# EPF-100_MP3.net
KiCad netlist of a schematic drawn in Altium Designer
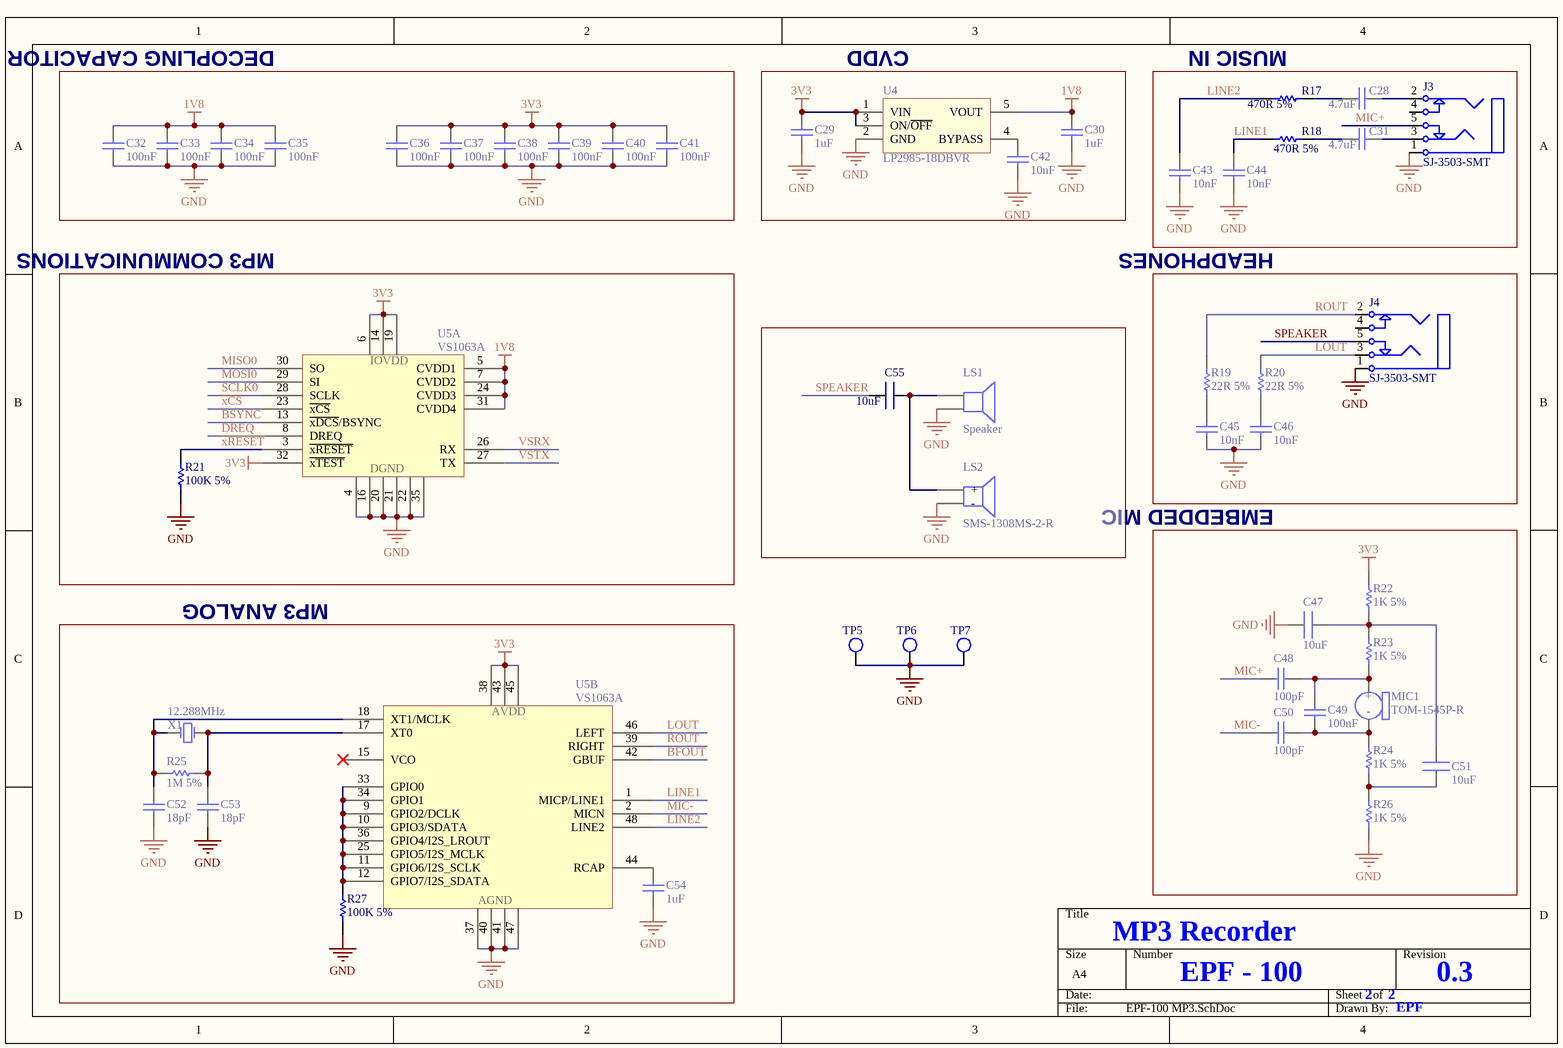
[diagram p0: EPF-100 MP3.SchDoc]

(export (version "E")
  (design (tool "Eeschema 10.0.6"))
  (components
    (comp (ref "C28")
      (value "4.7uF")
      (footprint "CAP0603")
      (description "X7R Ceramic Capacitors - SMD 0603")
      (fields (field (name "TOLERANCE") "X7R") (field (name "MANUFACTURER") "Murata Electronics"))
      (libsource (lib "Glober_Library") (part "CAP 4.7uF"))
    )
    (comp (ref "C29")
      (value "1uF")
      (footprint "CAP0603")
      (description "X7R Ceramic Capacitors - SMD 0603")
      (fields (field (name "TOLERANCE") "X7R") (field (name "MANUFACTURER") "TDK"))
      (libsource (lib "Glober_Library") (part "CAP 1uF"))
    )
    (comp (ref "C30")
      (value "1uF")
      (footprint "CAP0603")
      (description "X7R Ceramic Capacitors - SMD 0603")
      (fields (field (name "TOLERANCE") "X7R") (field (name "MANUFACTURER") "TDK"))
      (libsource (lib "Glober_Library") (part "CAP 1uF"))
    )
    (comp (ref "C31")
      (value "4.7uF")
      (footprint "CAP0603")
      (description "X7R Ceramic Capacitors - SMD 0603")
      (fields (field (name "TOLERANCE") "X7R") (field (name "MANUFACTURER") "Murata Electronics"))
      (libsource (lib "Glober_Library") (part "CAP 4.7uF"))
    )
    (comp (ref "C32")
      (value "100nF")
      (footprint "CAP0603")
      (description "X7R Ceramic Capacitors - SMD 0603")
      (fields (field (name "TOLERANCE") "X7R") (field (name "MANUFACTURER") "TDK"))
      (libsource (lib "Glober_Library") (part "CAP 100nF"))
    )
    (comp (ref "C33")
      (value "100nF")
      (footprint "CAP0603")
      (description "X7R Ceramic Capacitors - SMD 0603")
      (fields (field (name "TOLERANCE") "X7R") (field (name "MANUFACTURER") "TDK"))
      (libsource (lib "Glober_Library") (part "CAP 100nF"))
    )
    (comp (ref "C34")
      (value "100nF")
      (footprint "CAP0603")
      (description "X7R Ceramic Capacitors - SMD 0603")
      (fields (field (name "TOLERANCE") "X7R") (field (name "MANUFACTURER") "TDK"))
      (libsource (lib "Glober_Library") (part "CAP 100nF"))
    )
    (comp (ref "C35")
      (value "100nF")
      (footprint "CAP0603")
      (description "X7R Ceramic Capacitors - SMD 0603")
      (fields (field (name "TOLERANCE") "X7R") (field (name "MANUFACTURER") "TDK"))
      (libsource (lib "Glober_Library") (part "CAP 100nF"))
    )
    (comp (ref "C36")
      (value "100nF")
      (footprint "CAP0603")
      (description "X7R Ceramic Capacitors - SMD 0603")
      (fields (field (name "TOLERANCE") "X7R") (field (name "MANUFACTURER") "TDK"))
      (libsource (lib "Glober_Library") (part "CAP 100nF"))
    )
    (comp (ref "C37")
      (value "100nF")
      (footprint "CAP0603")
      (description "X7R Ceramic Capacitors - SMD 0603")
      (fields (field (name "TOLERANCE") "X7R") (field (name "MANUFACTURER") "TDK"))
      (libsource (lib "Glober_Library") (part "CAP 100nF"))
    )
    (comp (ref "C38")
      (value "100nF")
      (footprint "CAP0603")
      (description "X7R Ceramic Capacitors - SMD 0603")
      (fields (field (name "TOLERANCE") "X7R") (field (name "MANUFACTURER") "TDK"))
      (libsource (lib "Glober_Library") (part "CAP 100nF"))
    )
    (comp (ref "C39")
      (value "100nF")
      (footprint "CAP0603")
      (description "X7R Ceramic Capacitors - SMD 0603")
      (fields (field (name "TOLERANCE") "X7R") (field (name "MANUFACTURER") "TDK"))
      (libsource (lib "Glober_Library") (part "CAP 100nF"))
    )
    (comp (ref "C40")
      (value "100nF")
      (footprint "CAP0603")
      (description "X7R Ceramic Capacitors - SMD 0603")
      (fields (field (name "TOLERANCE") "X7R") (field (name "MANUFACTURER") "TDK"))
      (libsource (lib "Glober_Library") (part "CAP 100nF"))
    )
    (comp (ref "C41")
      (value "100nF")
      (footprint "CAP0603")
      (description "X7R Ceramic Capacitors - SMD 0603")
      (fields (field (name "TOLERANCE") "X7R") (field (name "MANUFACTURER") "TDK"))
      (libsource (lib "Glober_Library") (part "CAP 100nF"))
    )
    (comp (ref "C42")
      (value "10nF")
      (footprint "CAP0603")
      (description "X7R Ceramic Capacitors - SMD 0603")
      (fields (field (name "TOLERANCE") "X7R") (field (name "MANUFACTURER") "TDK"))
      (libsource (lib "Glober_Library") (part "CAP 10nF"))
    )
    (comp (ref "C43")
      (value "10nF")
      (footprint "CAP0603")
      (description "X7R Ceramic Capacitors - SMD 0603")
      (fields (field (name "TOLERANCE") "X7R") (field (name "MANUFACTURER") "TDK"))
      (libsource (lib "Glober_Library") (part "CAP 10nF"))
    )
    (comp (ref "C44")
      (value "10nF")
      (footprint "CAP0603")
      (description "X7R Ceramic Capacitors - SMD 0603")
      (fields (field (name "TOLERANCE") "X7R") (field (name "MANUFACTURER") "TDK"))
      (libsource (lib "Glober_Library") (part "CAP 10nF"))
    )
    (comp (ref "C45")
      (value "10nF")
      (footprint "CAP0603")
      (description "X7R Ceramic Capacitors - SMD 0603")
      (fields (field (name "TOLERANCE") "X7R") (field (name "MANUFACTURER") "TDK"))
      (libsource (lib "Glober_Library") (part "CAP 10nF"))
    )
    (comp (ref "C46")
      (value "10nF")
      (footprint "CAP0603")
      (description "X7R Ceramic Capacitors - SMD 0603")
      (fields (field (name "TOLERANCE") "X7R") (field (name "MANUFACTURER") "TDK"))
      (libsource (lib "Glober_Library") (part "CAP 10nF"))
    )
    (comp (ref "C47")
      (value "10uF")
      (footprint "CAP0805")
      (description "X5R Ceramic Capacitors - SMD 0805")
      (fields (field (name "TOLERANCE") "X5R"))
      (libsource (lib "Glober_Library") (part "CAP CER 0805 X5R 10uF 35V"))
    )
    (comp (ref "C48")
      (value "100pF")
      (footprint "CAP0603")
      (description "C0G Ceramic Capacitors - SMD 0603")
      (fields (field (name "TOLERANCE") "C0G") (field (name "MANUFACTURER") "TDK"))
      (libsource (lib "Glober_Library") (part "CAP 100pF"))
    )
    (comp (ref "C49")
      (value "100nF")
      (footprint "CAP0603")
      (description "X7R Ceramic Capacitors - SMD 0603")
      (fields (field (name "TOLERANCE") "X7R") (field (name "MANUFACTURER") "TDK"))
      (libsource (lib "Glober_Library") (part "CAP 100nF"))
    )
    (comp (ref "C50")
      (value "100pF")
      (footprint "CAP0603")
      (description "C0G Ceramic Capacitors - SMD 0603")
      (fields (field (name "TOLERANCE") "C0G") (field (name "MANUFACTURER") "TDK"))
      (libsource (lib "Glober_Library") (part "CAP 100pF"))
    )
    (comp (ref "C51")
      (value "10uF")
      (footprint "CAP0805")
      (description "X5R Ceramic Capacitors - SMD 0805")
      (fields (field (name "TOLERANCE") "X5R"))
      (libsource (lib "Glober_Library") (part "CAP CER 0805 X5R 10uF 35V"))
    )
    (comp (ref "C52")
      (value "18pF")
      (footprint "CAP0603")
      (description "C0G Ceramic Capacitors - SMD 0603")
      (fields (field (name "TOLERANCE") "C0G") (field (name "MANUFACTURER") "Murata"))
      (libsource (lib "Glober_Library") (part "CAP 18pF"))
    )
    (comp (ref "C53")
      (value "18pF")
      (footprint "CAP0603")
      (description "C0G Ceramic Capacitors - SMD 0603")
      (fields (field (name "TOLERANCE") "C0G") (field (name "MANUFACTURER") "Murata"))
      (libsource (lib "Glober_Library") (part "CAP 18pF"))
    )
    (comp (ref "C54")
      (value "1uF")
      (footprint "CAP0603")
      (description "X7R Ceramic Capacitors - SMD 0603")
      (fields (field (name "TOLERANCE") "X7R") (field (name "MANUFACTURER") "TDK"))
      (libsource (lib "Glober_Library") (part "CAP 1uF"))
    )
    (comp (ref "C55")
      (value "10uF")
      (footprint "CAP0805")
      (description "X5R Ceramic Capacitors - SMD 0805")
      (fields (field (name "TOLERANCE") "X5R"))
      (libsource (lib "Glober_Library") (part "CAP CER 0805 X5R 10uF 35V"))
    )
    (comp (ref "J3")
      (value "SJ-3503-SMT")
      (footprint "SJ-3503-SMT")
      (description "3-Conductor Jack with 2 break contacts (normals) and 2 auxiliary make contacts")
      (libsource (lib "Glober_Library") (part "SJ-3503-SMT"))
    )
    (comp (ref "J4")
      (value "SJ-3503-SMT")
      (footprint "SJ-3503-SMT")
      (description "3-Conductor Jack with 2 break contacts (normals) and 2 auxiliary make contacts")
      (libsource (lib "Glober_Library") (part "SJ-3503-SMT"))
    )
    (comp (ref "LS1")
      (value "Speaker")
      (footprint "HDR1X2 - Speaker")
      (description "Loudspeaker")
      (libsource (lib "Glober_Library") (part "Speaker"))
    )
    (comp (ref "LS2")
      (value "SMS-1308MS-2-R")
      (footprint "SMS-1308MS-2-R")
      (description "Loudspeaker")
      (fields (field (name "MANUFACTURER") "PUI Audio"))
      (libsource (lib "Glober_Library") (part "SMS-1308MS-2-R"))
    )
    (comp (ref "MIC1")
      (value "TOM-1545P-R")
      (footprint "TOM-154P-R")
      (libsource (lib "Glober_Library") (part "PTH ELECTRET MIC"))
    )
    (comp (ref "R17")
      (value "470R 5%")
      (footprint "RES0603")
      (description "5% Thick Film Resistors - SMD 0603")
      (fields (field (name "TOLERANCE") "5%") (field (name "MANUFACTURER") "Bourns"))
      (libsource (lib "Glober_Library") (part "RES 470R"))
    )
    (comp (ref "R18")
      (value "470R 5%")
      (footprint "RES0603")
      (description "5% Thick Film Resistors - SMD 0603")
      (fields (field (name "TOLERANCE") "5%") (field (name "MANUFACTURER") "Bourns"))
      (libsource (lib "Glober_Library") (part "RES 470R"))
    )
    (comp (ref "R19")
      (value "22R 5%")
      (footprint "RES0603")
      (description "5% Thick Film Resistors - SMD 0603")
      (fields (field (name "TOLERANCE") "5%") (field (name "MANUFACTURER") "Bourns"))
      (libsource (lib "Glober_Library") (part "RES 22R"))
    )
    (comp (ref "R20")
      (value "22R 5%")
      (footprint "RES0603")
      (description "5% Thick Film Resistors - SMD 0603")
      (fields (field (name "TOLERANCE") "5%") (field (name "MANUFACTURER") "Bourns"))
      (libsource (lib "Glober_Library") (part "RES 22R"))
    )
    (comp (ref "R21")
      (value "100K 5%")
      (footprint "RES0603")
      (description "5% Thick Film Resistors - SMD 0603")
      (fields (field (name "TOLERANCE") "5%") (field (name "MANUFACTURER") "Bourns"))
      (libsource (lib "Glober_Library") (part "RES 100K"))
    )
    (comp (ref "R22")
      (value "1K 5%")
      (footprint "RES0603")
      (description "5% Thick Film Resistors - SMD 0603")
      (fields (field (name "TOLERANCE") "5%") (field (name "MANUFACTURER") "Bourns"))
      (libsource (lib "Glober_Library") (part "RES 1K"))
    )
    (comp (ref "R23")
      (value "1K 5%")
      (footprint "RES0603")
      (description "5% Thick Film Resistors - SMD 0603")
      (fields (field (name "TOLERANCE") "5%") (field (name "MANUFACTURER") "Bourns"))
      (libsource (lib "Glober_Library") (part "RES 1K"))
    )
    (comp (ref "R24")
      (value "1K 5%")
      (footprint "RES0603")
      (description "5% Thick Film Resistors - SMD 0603")
      (fields (field (name "TOLERANCE") "5%") (field (name "MANUFACTURER") "Bourns"))
      (libsource (lib "Glober_Library") (part "RES 1K"))
    )
    (comp (ref "R25")
      (value "1M 5%")
      (footprint "RES0603")
      (description "5% Thick Film Resistors - SMD 0603")
      (fields (field (name "TOLERANCE") "5%") (field (name "MANUFACTURER") "Bourns"))
      (libsource (lib "Glober_Library") (part "RES 1M"))
    )
    (comp (ref "R26")
      (value "1K 5%")
      (footprint "RES0603")
      (description "5% Thick Film Resistors - SMD 0603")
      (fields (field (name "TOLERANCE") "5%") (field (name "MANUFACTURER") "Bourns"))
      (libsource (lib "Glober_Library") (part "RES 1K"))
    )
    (comp (ref "R27")
      (value "100K 5%")
      (footprint "RES0603")
      (description "5% Thick Film Resistors - SMD 0603")
      (fields (field (name "TOLERANCE") "5%") (field (name "MANUFACTURER") "Bourns"))
      (libsource (lib "Glober_Library") (part "RES 100K"))
    )
    (comp (ref "TP5")
      (value "PCB TEST POINT")
      (footprint "PCB TEST POINT")
      (libsource (lib "Glober_Library") (part "PCB TEST POINT"))
    )
    (comp (ref "TP6")
      (value "PCB TEST POINT")
      (footprint "PCB TEST POINT")
      (libsource (lib "Glober_Library") (part "PCB TEST POINT"))
    )
    (comp (ref "TP7")
      (value "PCB TEST POINT")
      (footprint "PCB TEST POINT")
      (libsource (lib "Glober_Library") (part "PCB TEST POINT"))
    )
    (comp (ref "U4")
      (value "LP2985-18DBVR")
      (footprint "SOT23-5BN")
      (description "1.8V Current 150mA")
      (fields (field (name "MANUFACTURER") "Texas Instruments"))
      (libsource (lib "GloberSchlib") (part "LP2985"))
    )
    (comp (ref "U5")
      (value "VS1063A")
      (footprint "TQFP48_N - VLSI")
      (description "MP3 Encoder/Decoder")
      (libsource (lib "Glober_Library") (part "VS1063A"))
    )
    (comp (ref "X1")
      (value "12.288MHz")
      (footprint "SMD XTAL ABM3B")
      (description "CERAMIC SURFACE MOUNT MICROPROCESSOR CRYSTAL")
      (fields (field (name "MANUFACTURER") "ABRACON"))
      (libsource (lib "Glober_Library") (part "SMD XTAL 12.288MHz ABM3B"))
    )
  )
  (nets
    (net (code "1") (name "/BFOUT") (class "Default")
      (node (ref "U5") (pin "42") (pinfunction "GBUF_42") (pintype "passive"))
    )
    (net (code "2") (name "/BSYNC") (class "Default")
      (node (ref "U5") (pin "13") (pinfunction "~{xDCS}/BSYNC_13") (pintype "passive"))
    )
    (net (code "3") (name "/DREQ") (class "Default")
      (node (ref "U5") (pin "8") (pinfunction "DREQ_8") (pintype "passive"))
    )
    (net (code "4") (name "/LINE1") (class "Default")
      (node (ref "C44") (pin "2") (pinfunction "2_2") (pintype "passive"))
      (node (ref "R18") (pin "1") (pinfunction "1_1") (pintype "passive"))
      (node (ref "U5") (pin "1") (pinfunction "MICP/LINE1_1") (pintype "passive"))
    )
    (net (code "5") (name "/LINE2") (class "Default")
      (node (ref "C43") (pin "2") (pinfunction "2_2") (pintype "passive"))
      (node (ref "R17") (pin "1") (pinfunction "1_1") (pintype "passive"))
      (node (ref "U5") (pin "48") (pinfunction "LINE2_48") (pintype "passive"))
    )
    (net (code "6") (name "/LOUT") (class "Default")
      (node (ref "J4") (pin "3") (pinfunction "3_3") (pintype "passive"))
      (node (ref "R20") (pin "1") (pinfunction "1_1") (pintype "passive"))
      (node (ref "U5") (pin "46") (pinfunction "LEFT_46") (pintype "passive"))
    )
    (net (code "7") (name "/MIC+") (class "Default")
      (node (ref "C48") (pin "2") (pinfunction "2_2") (pintype "passive"))
      (node (ref "J3") (pin "5") (pinfunction "5_5") (pintype "passive"))
    )
    (net (code "8") (name "/MIC-") (class "Default")
      (node (ref "C50") (pin "2") (pinfunction "2_2") (pintype "passive"))
      (node (ref "U5") (pin "2") (pinfunction "MICN_2") (pintype "passive"))
    )
    (net (code "9") (name "/MISO0") (class "Default")
      (node (ref "U5") (pin "30") (pinfunction "SO_30") (pintype "passive"))
    )
    (net (code "10") (name "/MOSI0") (class "Default")
      (node (ref "U5") (pin "29") (pinfunction "SI_29") (pintype "passive"))
    )
    (net (code "11") (name "/ROUT") (class "Default")
      (node (ref "J4") (pin "2") (pinfunction "2_2") (pintype "passive"))
      (node (ref "R19") (pin "1") (pinfunction "1_1") (pintype "passive"))
      (node (ref "U5") (pin "39") (pinfunction "RIGHT_39") (pintype "passive"))
    )
    (net (code "12") (name "/SCLK0") (class "Default")
      (node (ref "U5") (pin "28") (pinfunction "SCLK_28") (pintype "passive"))
    )
    (net (code "13") (name "/SPEAKER") (class "Default")
      (node (ref "C55") (pin "1") (pinfunction "0_1") (pintype "passive"))
      (node (ref "J4") (pin "5") (pinfunction "5_5") (pintype "passive"))
    )
    (net (code "14") (name "/VSRX") (class "Default")
      (node (ref "U5") (pin "26") (pinfunction "RX_26") (pintype "passive"))
    )
    (net (code "15") (name "/VSTX") (class "Default")
      (node (ref "U5") (pin "27") (pinfunction "TX_27") (pintype "passive"))
    )
    (net (code "16") (name "/~{xCS}") (class "Default")
      (node (ref "U5") (pin "23") (pinfunction "~{xCS}_23") (pintype "passive"))
    )
    (net (code "17") (name "/~{xRESET}") (class "Default")
      (node (ref "R21") (pin "2") (pinfunction "2_2") (pintype "passive"))
      (node (ref "U5") (pin "3") (pinfunction "~{xRESET}_3") (pintype "passive"))
    )
    (net (code "18") (name "1V8") (class "Default")
      (node (ref "C30") (pin "2") (pinfunction "2_2") (pintype "passive"))
      (node (ref "C32") (pin "2") (pinfunction "2_2") (pintype "passive"))
      (node (ref "C33") (pin "2") (pinfunction "2_2") (pintype "passive"))
      (node (ref "C34") (pin "2") (pinfunction "2_2") (pintype "passive"))
      (node (ref "C35") (pin "2") (pinfunction "2_2") (pintype "passive"))
      (node (ref "U4") (pin "5") (pinfunction "VOUT_5") (pintype "passive"))
      (node (ref "U5") (pin "24") (pinfunction "CVDD3_24") (pintype "passive"))
      (node (ref "U5") (pin "31") (pinfunction "CVDD4_31") (pintype "passive"))
      (node (ref "U5") (pin "5") (pinfunction "CVDD1_5") (pintype "passive"))
      (node (ref "U5") (pin "7") (pinfunction "CVDD2_7") (pintype "passive"))
    )
    (net (code "19") (name "3V3") (class "Default")
      (node (ref "C29") (pin "2") (pinfunction "2_2") (pintype "passive"))
      (node (ref "C36") (pin "2") (pinfunction "2_2") (pintype "passive"))
      (node (ref "C37") (pin "2") (pinfunction "2_2") (pintype "passive"))
      (node (ref "C38") (pin "2") (pinfunction "2_2") (pintype "passive"))
      (node (ref "C39") (pin "2") (pinfunction "2_2") (pintype "passive"))
      (node (ref "C40") (pin "2") (pinfunction "2_2") (pintype "passive"))
      (node (ref "C41") (pin "2") (pinfunction "2_2") (pintype "passive"))
      (node (ref "R22") (pin "2") (pinfunction "2_2") (pintype "passive"))
      (node (ref "U4") (pin "1") (pinfunction "VIN_1") (pintype "passive"))
      (node (ref "U4") (pin "3") (pinfunction "ON/~{OFF}_3") (pintype "passive"))
      (node (ref "U5") (pin "14") (pinfunction "IOVDD2_14") (pintype "passive"))
      (node (ref "U5") (pin "19") (pinfunction "IOVDD3_19") (pintype "passive"))
      (node (ref "U5") (pin "32") (pinfunction "~{xTEST}_32") (pintype "passive"))
      (node (ref "U5") (pin "38") (pinfunction "AVDD1_38") (pintype "passive"))
      (node (ref "U5") (pin "43") (pinfunction "AVDD2_43") (pintype "passive"))
      (node (ref "U5") (pin "45") (pinfunction "AVDD3_45") (pintype "passive"))
      (node (ref "U5") (pin "6") (pinfunction "IOVDD1_6") (pintype "passive"))
    )
    (net (code "20") (name "GND") (class "Default")
      (node (ref "C29") (pin "1") (pinfunction "1_1") (pintype "passive"))
      (node (ref "C30") (pin "1") (pinfunction "1_1") (pintype "passive"))
      (node (ref "C32") (pin "1") (pinfunction "1_1") (pintype "passive"))
      (node (ref "C33") (pin "1") (pinfunction "1_1") (pintype "passive"))
      (node (ref "C34") (pin "1") (pinfunction "1_1") (pintype "passive"))
      (node (ref "C35") (pin "1") (pinfunction "1_1") (pintype "passive"))
      (node (ref "C36") (pin "1") (pinfunction "1_1") (pintype "passive"))
      (node (ref "C37") (pin "1") (pinfunction "1_1") (pintype "passive"))
      (node (ref "C38") (pin "1") (pinfunction "1_1") (pintype "passive"))
      (node (ref "C39") (pin "1") (pinfunction "1_1") (pintype "passive"))
      (node (ref "C40") (pin "1") (pinfunction "1_1") (pintype "passive"))
      (node (ref "C41") (pin "1") (pinfunction "1_1") (pintype "passive"))
      (node (ref "C42") (pin "1") (pinfunction "1_1") (pintype "passive"))
      (node (ref "C43") (pin "1") (pinfunction "1_1") (pintype "passive"))
      (node (ref "C44") (pin "1") (pinfunction "1_1") (pintype "passive"))
      (node (ref "C45") (pin "2") (pinfunction "2_2") (pintype "passive"))
      (node (ref "C46") (pin "2") (pinfunction "2_2") (pintype "passive"))
      (node (ref "C47") (pin "2") (pinfunction "0_2") (pintype "passive"))
      (node (ref "C52") (pin "2") (pinfunction "2_2") (pintype "passive"))
      (node (ref "C53") (pin "2") (pinfunction "2_2") (pintype "passive"))
      (node (ref "C54") (pin "1") (pinfunction "1_1") (pintype "passive"))
      (node (ref "J3") (pin "1") (pinfunction "1_1") (pintype "passive"))
      (node (ref "J4") (pin "1") (pinfunction "1_1") (pintype "passive"))
      (node (ref "LS1") (pin "2") (pinfunction "2_2") (pintype "passive"))
      (node (ref "LS2") (pin "2") (pinfunction "-_2") (pintype "passive"))
      (node (ref "R21") (pin "1") (pinfunction "1_1") (pintype "passive"))
      (node (ref "R26") (pin "1") (pinfunction "1_1") (pintype "passive"))
      (node (ref "R27") (pin "1") (pinfunction "1_1") (pintype "passive"))
      (node (ref "TP5") (pin "1") (pinfunction "1_1") (pintype "passive"))
      (node (ref "TP6") (pin "1") (pinfunction "1_1") (pintype "passive"))
      (node (ref "TP7") (pin "1") (pinfunction "1_1") (pintype "passive"))
      (node (ref "U4") (pin "2") (pinfunction "GND_2") (pintype "passive"))
      (node (ref "U5") (pin "16") (pinfunction "DGND2_16") (pintype "passive"))
      (node (ref "U5") (pin "20") (pinfunction "DGND3_20") (pintype "passive"))
      (node (ref "U5") (pin "21") (pinfunction "DGND4_21") (pintype "passive"))
      (node (ref "U5") (pin "22") (pinfunction "DGND5_22") (pintype "passive"))
      (node (ref "U5") (pin "35") (pinfunction "DGND6_35") (pintype "passive"))
      (node (ref "U5") (pin "37") (pinfunction "AGND1_37") (pintype "passive"))
      (node (ref "U5") (pin "4") (pinfunction "DGND1_4") (pintype "passive"))
      (node (ref "U5") (pin "40") (pinfunction "AGND2_40") (pintype "passive"))
      (node (ref "U5") (pin "41") (pinfunction "AGND3_41") (pintype "passive"))
      (node (ref "U5") (pin "47") (pinfunction "AGND4_47") (pintype "passive"))
    )
    (net (code "21") (name "Net-(C28-Pad1)") (class "Default")
      (node (ref "C28") (pin "1") (pinfunction "1_1") (pintype "passive"))
      (node (ref "J3") (pin "2") (pinfunction "2_2") (pintype "passive"))
    )
    (net (code "22") (name "Net-(C28-Pad2)") (class "Default")
      (node (ref "C28") (pin "2") (pinfunction "2_2") (pintype "passive"))
      (node (ref "R17") (pin "2") (pinfunction "2_2") (pintype "passive"))
    )
    (net (code "23") (name "Net-(C31-Pad1)") (class "Default")
      (node (ref "C31") (pin "1") (pinfunction "1_1") (pintype "passive"))
      (node (ref "J3") (pin "3") (pinfunction "3_3") (pintype "passive"))
    )
    (net (code "24") (name "Net-(C31-Pad2)") (class "Default")
      (node (ref "C31") (pin "2") (pinfunction "2_2") (pintype "passive"))
      (node (ref "R18") (pin "2") (pinfunction "2_2") (pintype "passive"))
    )
    (net (code "25") (name "Net-(C45-Pad1)") (class "Default")
      (node (ref "C45") (pin "1") (pinfunction "1_1") (pintype "passive"))
      (node (ref "R19") (pin "2") (pinfunction "2_2") (pintype "passive"))
    )
    (net (code "26") (name "Net-(C46-Pad1)") (class "Default")
      (node (ref "C46") (pin "1") (pinfunction "1_1") (pintype "passive"))
      (node (ref "R20") (pin "2") (pinfunction "2_2") (pintype "passive"))
    )
    (net (code "27") (name "Net-(C47-0-Pad1)") (class "Default")
      (node (ref "C47") (pin "1") (pinfunction "0_1") (pintype "passive"))
      (node (ref "C51") (pin "1") (pinfunction "0_1") (pintype "passive"))
      (node (ref "R22") (pin "1") (pinfunction "1_1") (pintype "passive"))
      (node (ref "R23") (pin "2") (pinfunction "2_2") (pintype "passive"))
    )
    (net (code "28") (name "Net-(C51-0-Pad2)") (class "Default")
      (node (ref "C51") (pin "2") (pinfunction "0_2") (pintype "passive"))
      (node (ref "R24") (pin "1") (pinfunction "1_1") (pintype "passive"))
      (node (ref "R26") (pin "2") (pinfunction "2_2") (pintype "passive"))
    )
    (net (code "29") (name "Net-(LS2-+)") (class "Default")
      (node (ref "C55") (pin "2") (pinfunction "0_2") (pintype "passive"))
      (node (ref "LS1") (pin "1") (pinfunction "1_1") (pintype "passive"))
      (node (ref "LS2") (pin "1") (pinfunction "+_1") (pintype "passive"))
    )
    (net (code "30") (name "Net-(MIC1-Term_+)") (class "Default")
      (node (ref "C48") (pin "1") (pinfunction "1_1") (pintype "passive"))
      (node (ref "C49") (pin "2") (pinfunction "2_2") (pintype "passive"))
      (node (ref "MIC1") (pin "1") (pinfunction "Term_+_1") (pintype "passive"))
      (node (ref "R23") (pin "1") (pinfunction "1_1") (pintype "passive"))
    )
    (net (code "31") (name "Net-(MIC1-Term_-)") (class "Default")
      (node (ref "C49") (pin "1") (pinfunction "1_1") (pintype "passive"))
      (node (ref "C50") (pin "1") (pinfunction "1_1") (pintype "passive"))
      (node (ref "MIC1") (pin "2") (pinfunction "Term_-_2") (pintype "passive"))
      (node (ref "R24") (pin "2") (pinfunction "2_2") (pintype "passive"))
    )
    (net (code "32") (name "Net-(U4-BYPASS)") (class "Default")
      (node (ref "C42") (pin "2") (pinfunction "2_2") (pintype "passive"))
      (node (ref "U4") (pin "4") (pinfunction "BYPASS_4") (pintype "passive"))
    )
    (net (code "33") (name "Net-(U5B-GPIO0)") (class "Default")
      (node (ref "R27") (pin "2") (pinfunction "2_2") (pintype "passive"))
      (node (ref "U5") (pin "10") (pinfunction "GPIO3/SDATA_10") (pintype "passive"))
      (node (ref "U5") (pin "11") (pinfunction "GPIO6/I2S_SCLK_11") (pintype "passive"))
      (node (ref "U5") (pin "12") (pinfunction "GPIO7/I2S_SDATA_12") (pintype "passive"))
      (node (ref "U5") (pin "25") (pinfunction "GPIO5/I2S_MCLK_25") (pintype "passive"))
      (node (ref "U5") (pin "33") (pinfunction "GPIO0_33") (pintype "passive"))
      (node (ref "U5") (pin "34") (pinfunction "GPIO1_34") (pintype "passive"))
      (node (ref "U5") (pin "36") (pinfunction "GPIO4/I2S_LROUT_36") (pintype "passive"))
      (node (ref "U5") (pin "9") (pinfunction "GPIO2/DCLK_9") (pintype "passive"))
    )
    (net (code "34") (name "Net-(U5B-RCAP)") (class "Default")
      (node (ref "C54") (pin "2") (pinfunction "2_2") (pintype "passive"))
      (node (ref "U5") (pin "44") (pinfunction "RCAP_44") (pintype "passive"))
    )
    (net (code "35") (name "Net-(U5B-XT0)") (class "Default")
      (node (ref "C53") (pin "1") (pinfunction "1_1") (pintype "passive"))
      (node (ref "R25") (pin "1") (pinfunction "1_1") (pintype "passive"))
      (node (ref "U5") (pin "17") (pinfunction "XT0_17") (pintype "passive"))
      (node (ref "X1") (pin "1") (pinfunction "0_1") (pintype "passive"))
    )
    (net (code "36") (name "Net-(U5B-XT1{slash}MCLK)") (class "Default")
      (node (ref "C52") (pin "1") (pinfunction "1_1") (pintype "passive"))
      (node (ref "R25") (pin "2") (pinfunction "2_2") (pintype "passive"))
      (node (ref "U5") (pin "18") (pinfunction "XT1/MCLK_18") (pintype "passive"))
      (node (ref "X1") (pin "3") (pinfunction "0_3") (pintype "passive"))
    )
    (net (code "37") (name "unconnected-(J3-Pad4)") (class "Default")
      (node (ref "J3") (pin "4") (pinfunction "4_4") (pintype "passive"))
    )
    (net (code "38") (name "unconnected-(J4-Pad4)") (class "Default")
      (node (ref "J4") (pin "4") (pinfunction "4_4") (pintype "passive"))
    )
    (net (code "39") (name "unconnected-(U5B-VCO-Pad15)") (class "Default")
      (node (ref "U5") (pin "15") (pinfunction "VCO_15") (pintype "passive+no_connect"))
    )
  )
)
